# design.net
KiCad netlist of a schematic drawn in EasyEDA Pro
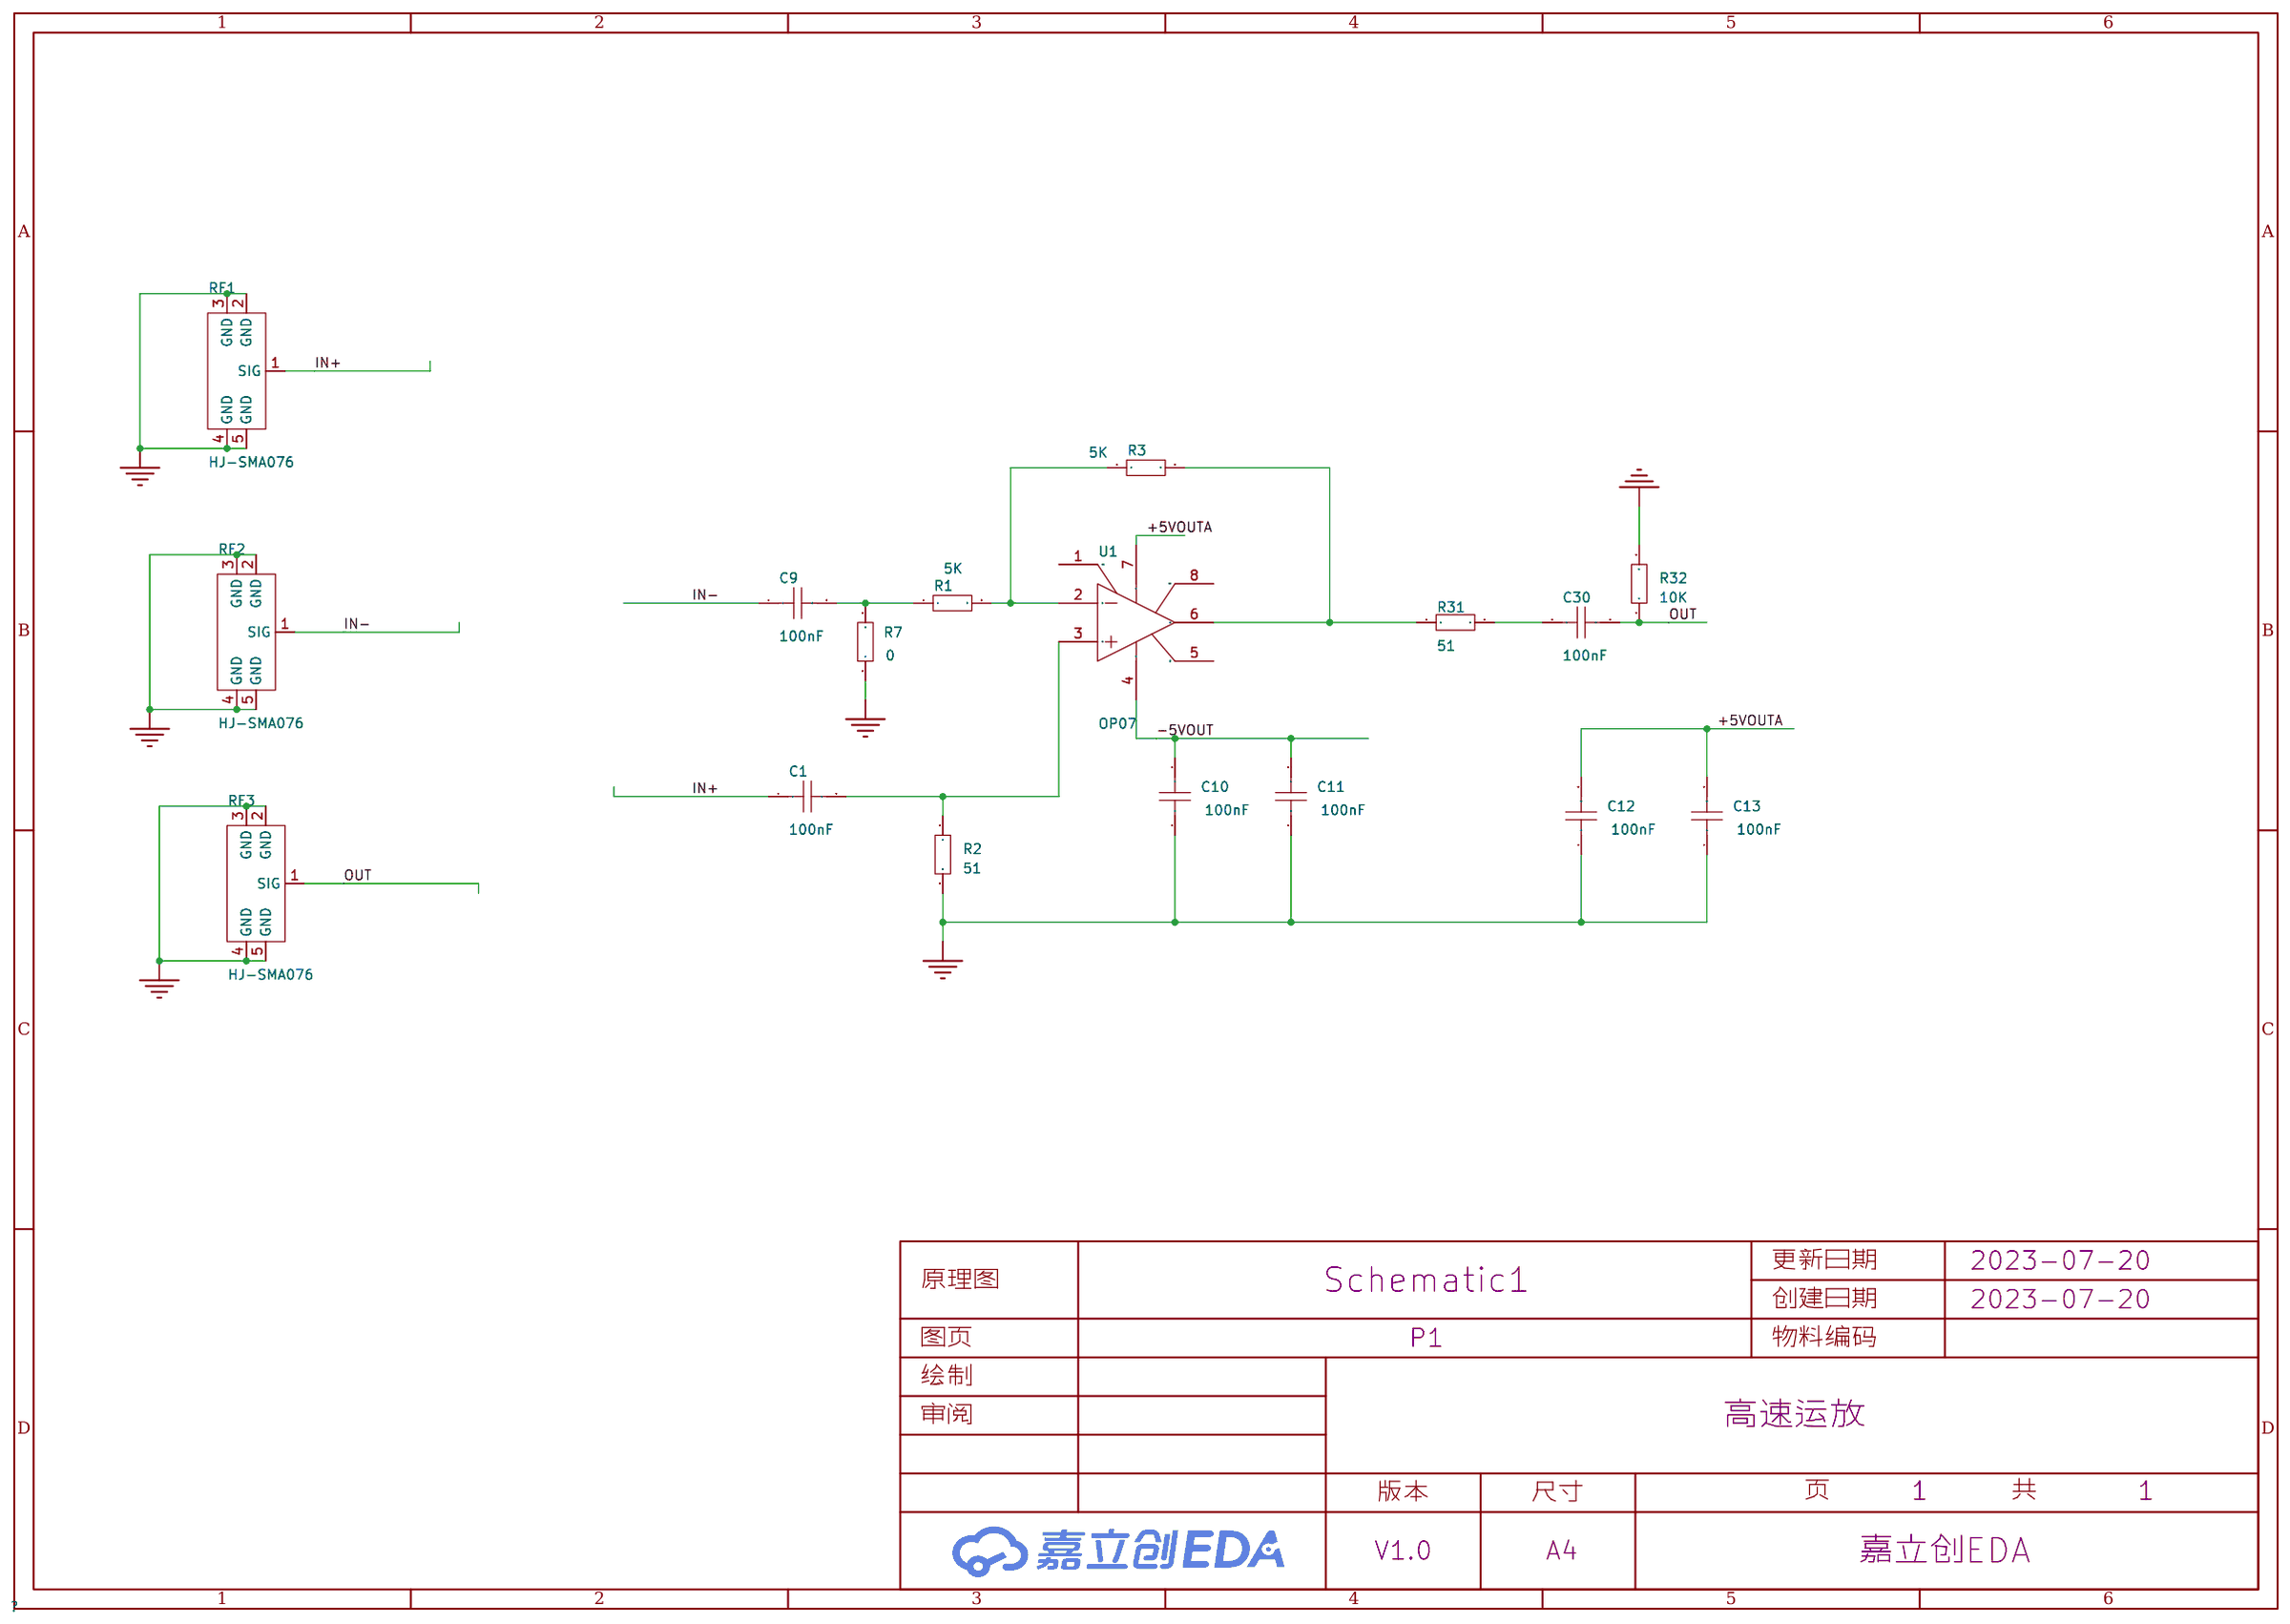
[diagram p0: P1]
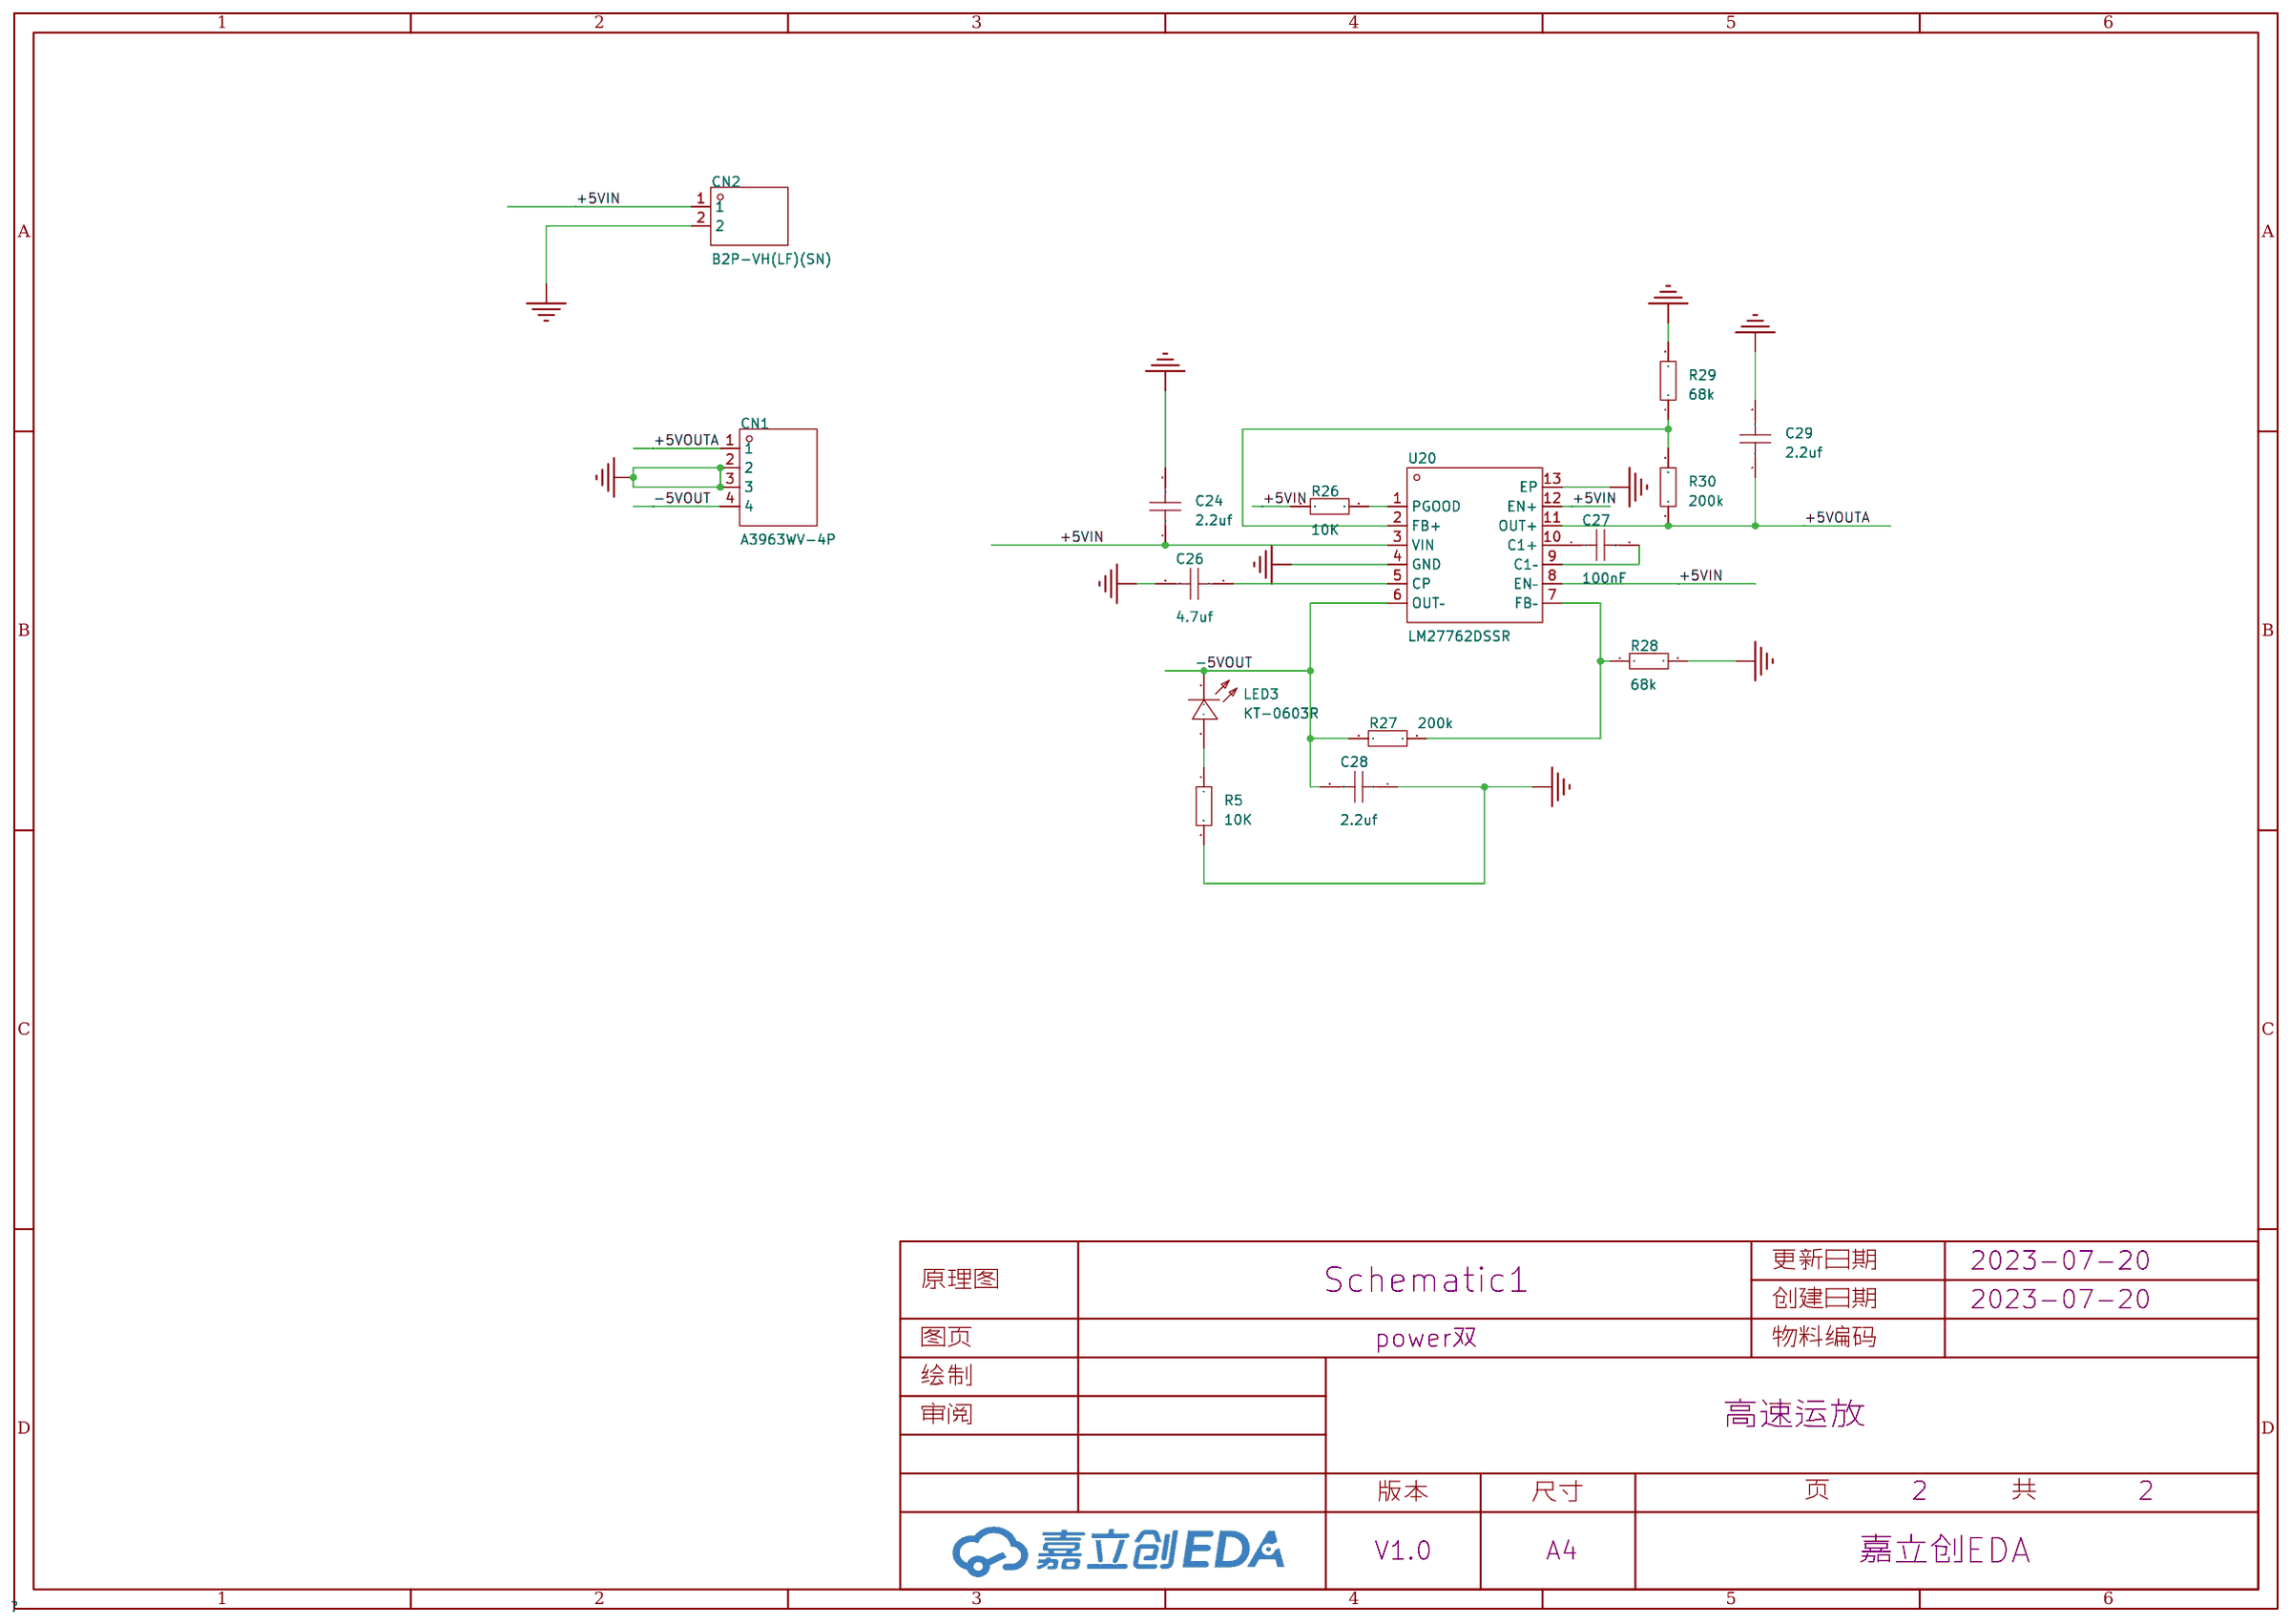
[diagram p1: power双]
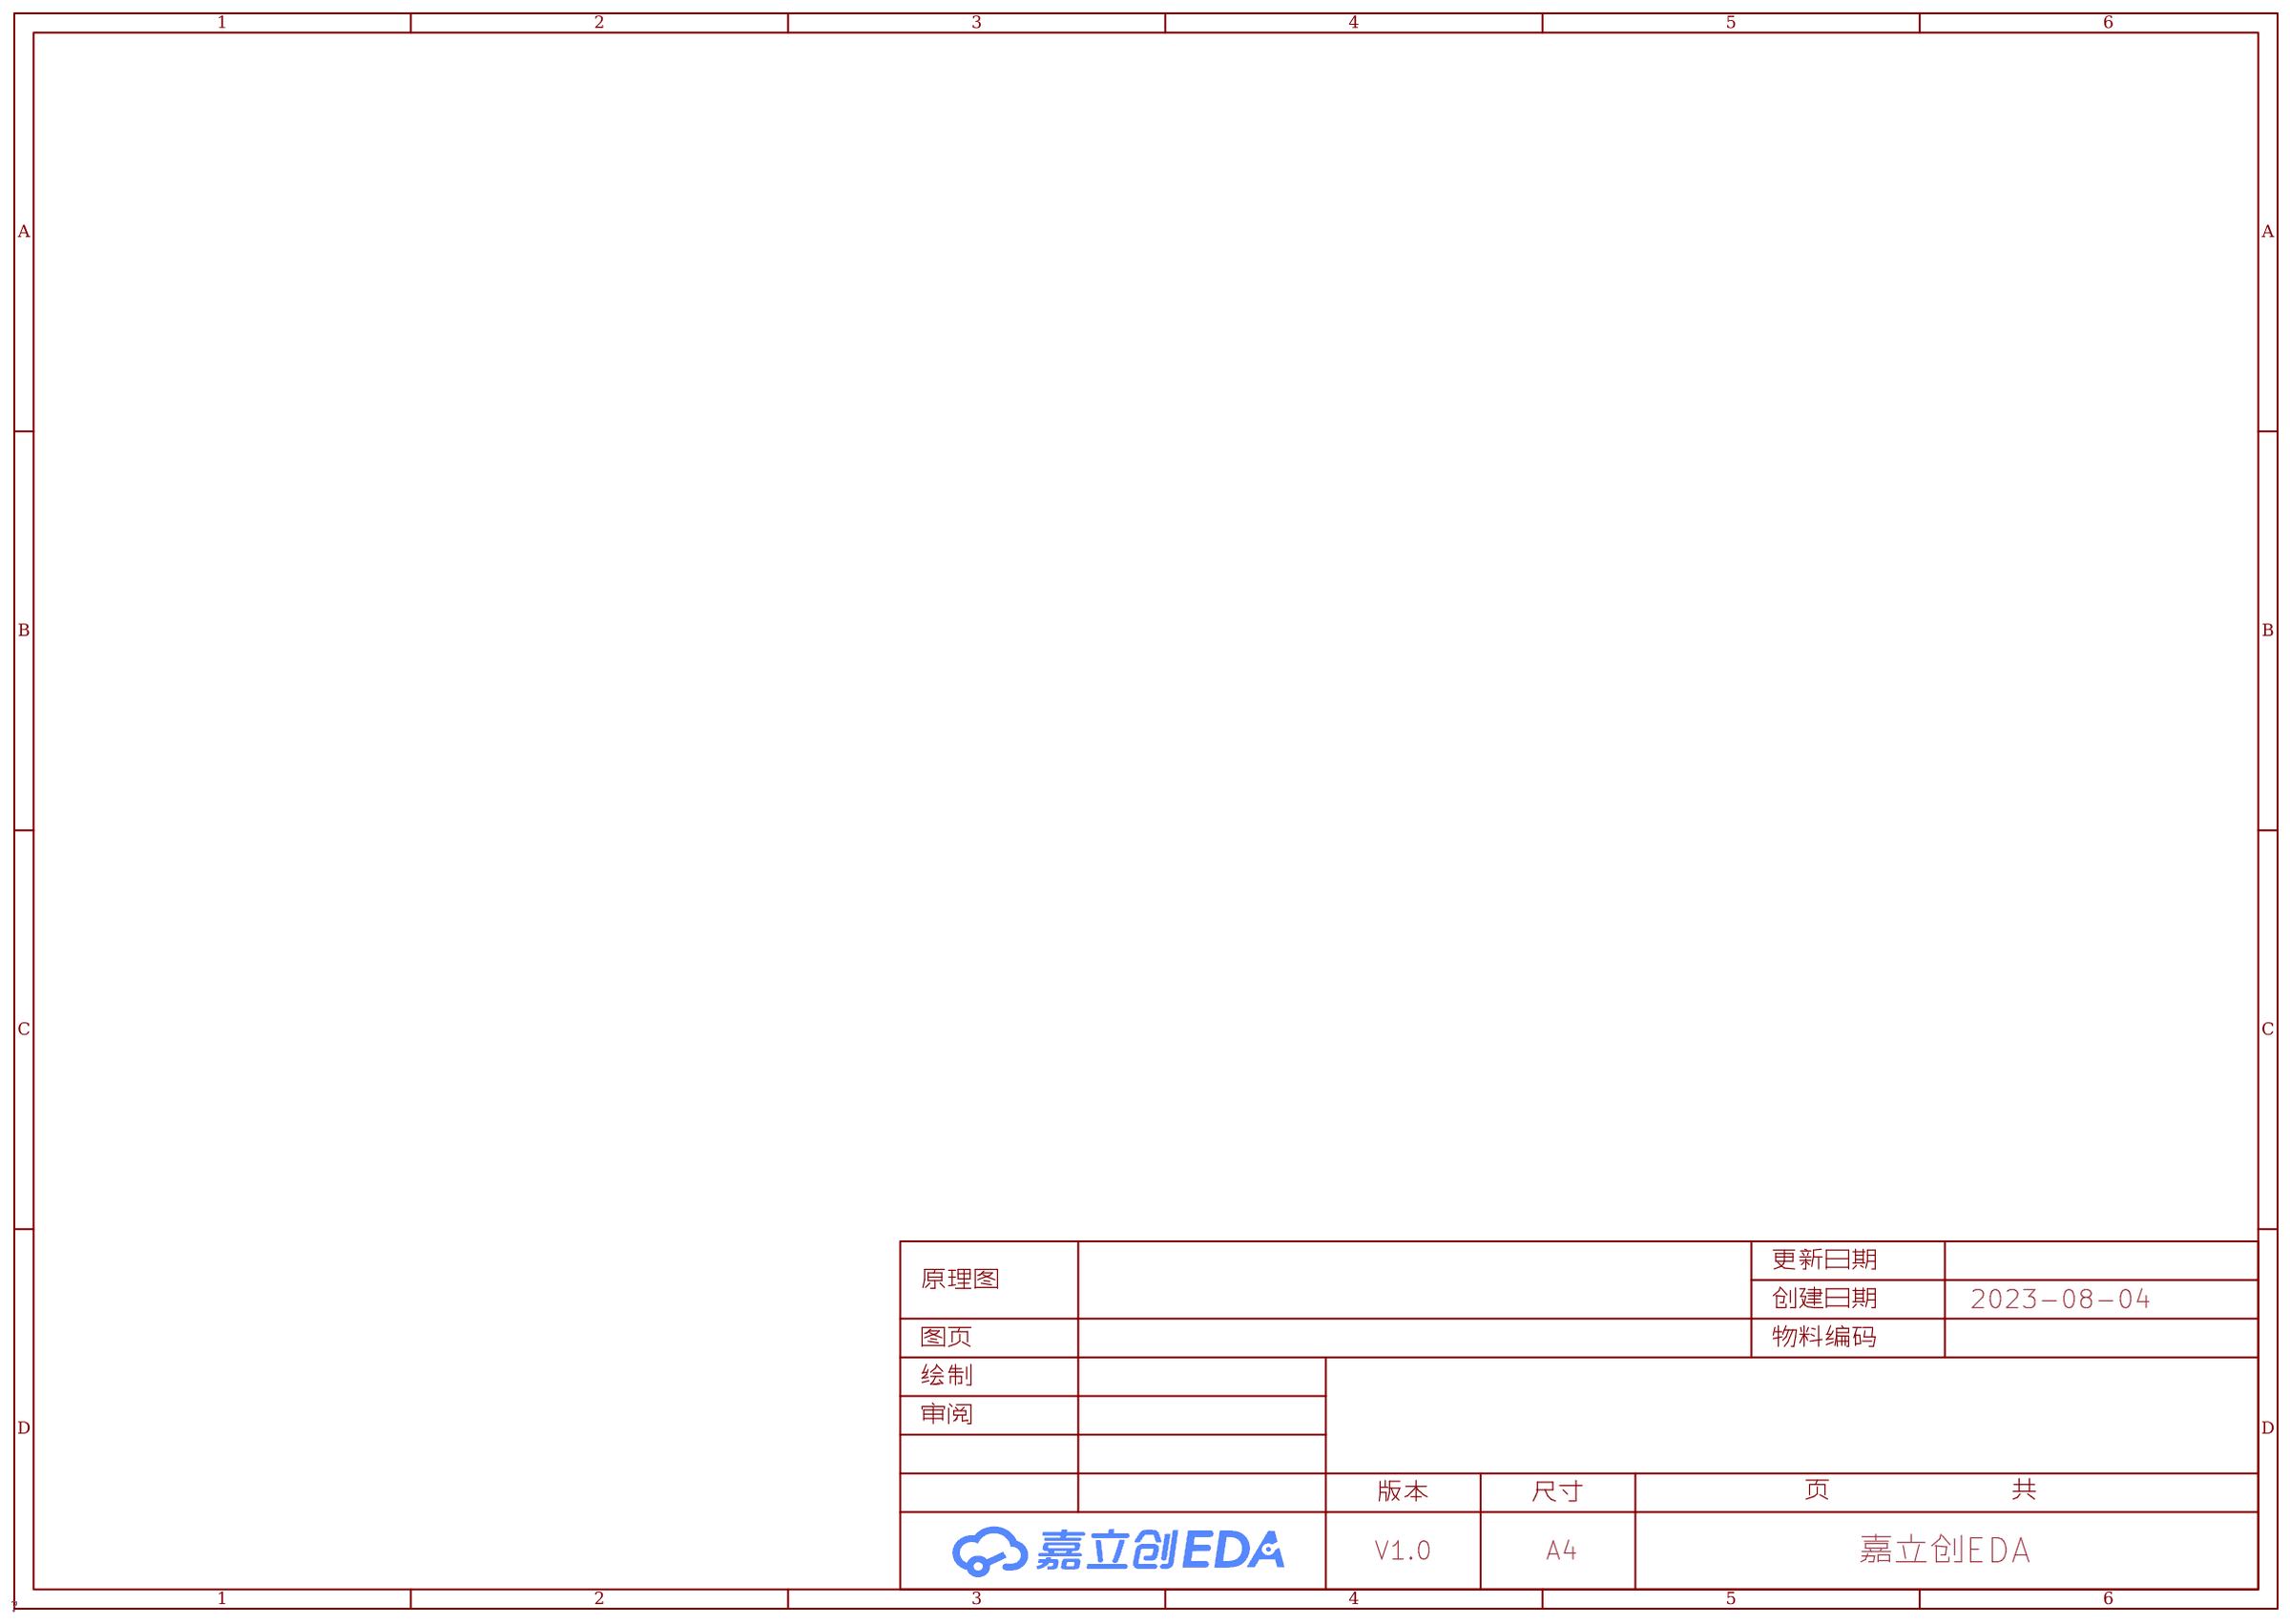
[diagram p2: P3]

(export (version "E")
  (design (tool "Eeschema 10.0.6"))
  (components
    (comp (ref "C1")
      (value "100nF")
      (footprint "easyedapro:C0603")
      (libsource (lib "easyedapro") (part "CapAcitance"))
    )
    (comp (ref "C9")
      (value "100nF")
      (footprint "easyedapro:C0603")
      (libsource (lib "easyedapro") (part "CapAcitance"))
    )
    (comp (ref "C10")
      (value "100nF")
      (footprint "easyedapro:C0603")
      (libsource (lib "easyedapro") (part "CapAcitance"))
    )
    (comp (ref "C11")
      (value "100nF")
      (footprint "easyedapro:C0603")
      (libsource (lib "easyedapro") (part "CapAcitance"))
    )
    (comp (ref "C12")
      (value "100nF")
      (footprint "easyedapro:C0603")
      (libsource (lib "easyedapro") (part "CapAcitance"))
    )
    (comp (ref "C13")
      (value "100nF")
      (footprint "easyedapro:C0603")
      (libsource (lib "easyedapro") (part "CapAcitance"))
    )
    (comp (ref "C30")
      (value "100nF")
      (footprint "easyedapro:C0603")
      (libsource (lib "easyedapro") (part "CapAcitance"))
    )
    (comp (ref "R1") (value "5K") (footprint "easyedapro:R0603") (libsource (lib "easyedapro") (part "电阻")))
    (comp (ref "R2") (value "51") (footprint "easyedapro:R0603") (libsource (lib "easyedapro") (part "电阻")))
    (comp (ref "R3") (value "5K") (footprint "easyedapro:R0603") (libsource (lib "easyedapro") (part "电阻")))
    (comp (ref "R7") (value "0") (footprint "easyedapro:R0603") (libsource (lib "easyedapro") (part "电阻")))
    (comp (ref "R31") (value "51") (footprint "easyedapro:R0603") (libsource (lib "easyedapro") (part "电阻")))
    (comp (ref "R32") (value "10K") (footprint "easyedapro:R0603") (libsource (lib "easyedapro") (part "电阻")))
    (comp (ref "RF1")
      (value "HJ-SMA076")
      (footprint "easyedapro:SMA-SMD_HJ-SMA076")
      (description "连接器类型:板端;射频系列:SMA;接口类型:内孔;端口数量:1;阻抗:-;频率-最大值:-;样式:偏脚;接口直径:-;接口长度/高度:-;工作温度范围:-;")
      (fields (field (name "Manufacturer") "皇捷"))
      (libsource (lib "easyedapro") (part "HJ-SMA076"))
    )
    (comp (ref "RF2")
      (value "HJ-SMA076")
      (footprint "easyedapro:SMA-SMD_HJ-SMA076")
      (description "连接器类型:板端;射频系列:SMA;接口类型:内孔;端口数量:1;阻抗:-;频率-最大值:-;样式:偏脚;接口直径:-;接口长度/高度:-;工作温度范围:-;")
      (fields (field (name "Manufacturer") "皇捷"))
      (libsource (lib "easyedapro") (part "HJ-SMA076"))
    )
    (comp (ref "RF3")
      (value "HJ-SMA076")
      (footprint "easyedapro:SMA-SMD_HJ-SMA076")
      (description "连接器类型:板端;射频系列:SMA;接口类型:内孔;端口数量:1;阻抗:-;频率-最大值:-;样式:偏脚;接口直径:-;接口长度/高度:-;工作温度范围:-;")
      (fields (field (name "Manufacturer") "皇捷"))
      (libsource (lib "easyedapro") (part "HJ-SMA076"))
    )
    (comp (ref "U1")
      (value "OP07")
      (footprint "easyedapro:SOP-8_L4.9-W3.9-P1.27-LS6.0-BL")
      (description "放大器组数:-;")
      (fields (field (name "Manufacturer") "杭州瑞盟"))
      (libsource (lib "easyedapro") (part "OP07"))
    )
    (comp (ref "C24")
      (value "2.2uf")
      (footprint "easyedapro:C0603")
      (libsource (lib "easyedapro") (part "CapAcitance"))
    )
    (comp (ref "C26")
      (value "4.7uf")
      (footprint "easyedapro:C0603")
      (libsource (lib "easyedapro") (part "CapAcitance"))
    )
    (comp (ref "C27")
      (value "100nF")
      (footprint "easyedapro:C0603")
      (libsource (lib "easyedapro") (part "CapAcitance"))
    )
    (comp (ref "C28")
      (value "2.2uf")
      (footprint "easyedapro:C0603")
      (libsource (lib "easyedapro") (part "CapAcitance"))
    )
    (comp (ref "C29")
      (value "2.2uf")
      (footprint "easyedapro:C0603")
      (libsource (lib "easyedapro") (part "CapAcitance"))
    )
    (comp (ref "CN1")
      (value "A3963WV-4P")
      (footprint "easyedapro:CONN-TH_A3963WV-4P")
      (description "参考系列:VH;间距:3.96mm;插针结构:1x4P;排数:1;每排PIN数:4;行距:-;安装方式:-;触头材质:黄铜;")
      (fields (field (name "Manufacturer") "CJT(长江连接器)"))
      (libsource (lib "easyedapro") (part "A3963WV-4P"))
    )
    (comp (ref "CN2")
      (value "B2P-VH(LF)(SN)")
      (footprint "easyedapro:CONN-TH_B2P-VH-LF-SN")
      (description "参考系列:VH;间距:3.96mm;插针结构:1x2P;排数:1;每排PIN数:2;行距:-;安装方式:-;触头材质:黄铜;")
      (fields (field (name "Manufacturer") "JST"))
      (libsource (lib "easyedapro") (part "B2P-VH (LF)(SN)"))
    )
    (comp (ref "LED3")
      (value "KT-0603R")
      (footprint "easyedapro:LED0603-RD")
      (description "发光颜色:红灯;二极管配置:-;透镜颜色:-;主波长:-;色温:-;功率:-;发光角度:-;安装方式:-;工作温度:-40℃~+85℃;")
      (fields (field (name "Manufacturer") "KENTO"))
      (libsource (lib "easyedapro") (part "KT-0603R"))
    )
    (comp (ref "R5") (value "10K") (footprint "easyedapro:R0603") (libsource (lib "easyedapro") (part "电阻")))
    (comp (ref "R26") (value "10K") (footprint "easyedapro:R0603") (libsource (lib "easyedapro") (part "电阻")))
    (comp (ref "R27")
      (value "200k")
      (footprint "easyedapro:R0603")
      (libsource (lib "easyedapro") (part "电阻"))
    )
    (comp (ref "R28") (value "68k") (footprint "easyedapro:R0603") (libsource (lib "easyedapro") (part "电阻")))
    (comp (ref "R29") (value "68k") (footprint "easyedapro:R0603") (libsource (lib "easyedapro") (part "电阻")))
    (comp (ref "R30")
      (value "200k")
      (footprint "easyedapro:R0603")
      (libsource (lib "easyedapro") (part "电阻"))
    )
    (comp (ref "U20")
      (value "LM27762DSSR")
      (footprint "easyedapro:WSON-12_L3.0-W2.0-P0.50-BL-EP")
      (description "功能类型:电荷泵;同步整流:否;输出通道数:2;拓扑结构:-;输入电压:2.7V~5.5V;输出电压:-5V~-1.5V；1.5V~5V;输出电流(最大值):250mA;开关频率:2.3MHz;")
      (fields (field (name "Manufacturer") "TI(德州仪器)"))
      (libsource (lib "easyedapro") (part "LM27762DSSR"))
    )
  )
  (nets
    (net (code "1") (name "+5VIN") (class "Default")
      (node (ref "C24") (pin "1") (pinfunction "1_1") (pintype "input"))
      (node (ref "CN2") (pin "1") (pinfunction "1_1") (pintype "input"))
      (node (ref "R26") (pin "1") (pinfunction "1_1") (pintype "input"))
      (node (ref "U20") (pin "12") (pinfunction "EN+_12") (pintype "input"))
      (node (ref "U20") (pin "3") (pinfunction "VIN_3") (pintype "input"))
      (node (ref "U20") (pin "8") (pinfunction "EN–_8") (pintype "input"))
    )
    (net (code "2") (name "+5VOUTA") (class "Default")
      (node (ref "C12") (pin "2") (pinfunction "2_2") (pintype "input"))
      (node (ref "C13") (pin "2") (pinfunction "2_2") (pintype "input"))
      (node (ref "C29") (pin "1") (pinfunction "1_1") (pintype "input"))
      (node (ref "CN1") (pin "1") (pinfunction "1_1") (pintype "input"))
      (node (ref "R30") (pin "1") (pinfunction "1_1") (pintype "input"))
      (node (ref "U1") (pin "7") (pinfunction "V+_7") (pintype "input"))
      (node (ref "U20") (pin "11") (pinfunction "OUT+_11") (pintype "input"))
    )
    (net (code "3") (name "-5VOUT") (class "Default")
      (node (ref "C10") (pin "2") (pinfunction "2_2") (pintype "input"))
      (node (ref "C11") (pin "2") (pinfunction "2_2") (pintype "input"))
      (node (ref "C28") (pin "2") (pinfunction "2_2") (pintype "input"))
      (node (ref "CN1") (pin "4") (pinfunction "4_4") (pintype "input"))
      (node (ref "LED3") (pin "1") (pinfunction "K_1") (pintype "input"))
      (node (ref "R27") (pin "1") (pinfunction "1_1") (pintype "input"))
      (node (ref "U1") (pin "4") (pinfunction "V-_4") (pintype "input"))
      (node (ref "U20") (pin "6") (pinfunction "OUT–_6") (pintype "input"))
    )
    (net (code "4") (name "GND") (class "Default")
      (node (ref "C10") (pin "1") (pinfunction "1_1") (pintype "input"))
      (node (ref "C11") (pin "1") (pinfunction "1_1") (pintype "input"))
      (node (ref "C12") (pin "1") (pinfunction "1_1") (pintype "input"))
      (node (ref "C13") (pin "1") (pinfunction "1_1") (pintype "input"))
      (node (ref "C24") (pin "2") (pinfunction "2_2") (pintype "input"))
      (node (ref "C26") (pin "2") (pinfunction "2_2") (pintype "input"))
      (node (ref "C28") (pin "1") (pinfunction "1_1") (pintype "input"))
      (node (ref "C29") (pin "2") (pinfunction "2_2") (pintype "input"))
      (node (ref "CN1") (pin "2") (pinfunction "2_2") (pintype "input"))
      (node (ref "CN1") (pin "3") (pinfunction "3_3") (pintype "input"))
      (node (ref "CN2") (pin "2") (pinfunction "2_2") (pintype "input"))
      (node (ref "R2") (pin "2") (pinfunction "2_2") (pintype "input"))
      (node (ref "R28") (pin "2") (pinfunction "2_2") (pintype "input"))
      (node (ref "R29") (pin "2") (pinfunction "2_2") (pintype "input"))
      (node (ref "R32") (pin "2") (pinfunction "2_2") (pintype "input"))
      (node (ref "R5") (pin "2") (pinfunction "2_2") (pintype "input"))
      (node (ref "R7") (pin "1") (pinfunction "1_1") (pintype "input"))
      (node (ref "RF1") (pin "2") (pinfunction "GND_2") (pintype "input"))
      (node (ref "RF1") (pin "3") (pinfunction "GND_3") (pintype "input"))
      (node (ref "RF1") (pin "4") (pinfunction "GND_4") (pintype "input"))
      (node (ref "RF1") (pin "5") (pinfunction "GND_5") (pintype "input"))
      (node (ref "RF2") (pin "2") (pinfunction "GND_2") (pintype "input"))
      (node (ref "RF2") (pin "3") (pinfunction "GND_3") (pintype "input"))
      (node (ref "RF2") (pin "4") (pinfunction "GND_4") (pintype "input"))
      (node (ref "RF2") (pin "5") (pinfunction "GND_5") (pintype "input"))
      (node (ref "RF3") (pin "2") (pinfunction "GND_2") (pintype "input"))
      (node (ref "RF3") (pin "3") (pinfunction "GND_3") (pintype "input"))
      (node (ref "RF3") (pin "4") (pinfunction "GND_4") (pintype "input"))
      (node (ref "RF3") (pin "5") (pinfunction "GND_5") (pintype "input"))
      (node (ref "U20") (pin "13") (pinfunction "EP_13") (pintype "input"))
      (node (ref "U20") (pin "4") (pinfunction "GND_4") (pintype "input"))
    )
    (net (code "5") (name "IN+") (class "Default")
      (node (ref "C1") (pin "1") (pinfunction "1_1") (pintype "input"))
      (node (ref "RF1") (pin "1") (pinfunction "SIG_1") (pintype "input"))
    )
    (net (code "6") (name "IN-") (class "Default")
      (node (ref "C9") (pin "1") (pinfunction "1_1") (pintype "input"))
      (node (ref "RF2") (pin "1") (pinfunction "SIG_1") (pintype "input"))
    )
    (net (code "7") (name "Net-(C9-Pad2)") (class "Default")
      (node (ref "C9") (pin "2") (pinfunction "2_2") (pintype "input"))
      (node (ref "R1") (pin "1") (pinfunction "1_1") (pintype "input"))
      (node (ref "R7") (pin "2") (pinfunction "2_2") (pintype "input"))
    )
    (net (code "8") (name "Net-(C30-Pad1)") (class "Default")
      (node (ref "C30") (pin "1") (pinfunction "1_1") (pintype "input"))
      (node (ref "R31") (pin "1") (pinfunction "1_1") (pintype "input"))
    )
    (net (code "9") (name "Net-(LED3-A)") (class "Default")
      (node (ref "LED3") (pin "2") (pinfunction "A_2") (pintype "input"))
      (node (ref "R5") (pin "1") (pinfunction "1_1") (pintype "input"))
    )
    (net (code "10") (name "Net-(U1-IN+)") (class "Default")
      (node (ref "C1") (pin "2") (pinfunction "2_2") (pintype "input"))
      (node (ref "R2") (pin "1") (pinfunction "1_1") (pintype "input"))
      (node (ref "U1") (pin "3") (pinfunction "IN+_3") (pintype "input"))
    )
    (net (code "11") (name "Net-(U1-IN-)") (class "Default")
      (node (ref "R1") (pin "2") (pinfunction "2_2") (pintype "input"))
      (node (ref "R3") (pin "1") (pinfunction "1_1") (pintype "input"))
      (node (ref "U1") (pin "2") (pinfunction "IN-_2") (pintype "input"))
    )
    (net (code "12") (name "Net-(U1-OUT)") (class "Default")
      (node (ref "R3") (pin "2") (pinfunction "2_2") (pintype "input"))
      (node (ref "R31") (pin "2") (pinfunction "2_2") (pintype "input"))
      (node (ref "U1") (pin "6") (pinfunction "OUT_6") (pintype "output"))
    )
    (net (code "13") (name "Net-(U20-C1+)") (class "Default")
      (node (ref "C27") (pin "1") (pinfunction "1_1") (pintype "input"))
      (node (ref "U20") (pin "10") (pinfunction "C1+_10") (pintype "input"))
    )
    (net (code "14") (name "Net-(U20-C1–)") (class "Default")
      (node (ref "C27") (pin "2") (pinfunction "2_2") (pintype "input"))
      (node (ref "U20") (pin "9") (pinfunction "C1–_9") (pintype "input"))
    )
    (net (code "15") (name "Net-(U20-CP)") (class "Default")
      (node (ref "C26") (pin "1") (pinfunction "1_1") (pintype "input"))
      (node (ref "U20") (pin "5") (pinfunction "CP_5") (pintype "input"))
    )
    (net (code "16") (name "Net-(U20-FB+)") (class "Default")
      (node (ref "R29") (pin "1") (pinfunction "1_1") (pintype "input"))
      (node (ref "R30") (pin "2") (pinfunction "2_2") (pintype "input"))
      (node (ref "U20") (pin "2") (pinfunction "FB+_2") (pintype "input"))
    )
    (net (code "17") (name "Net-(U20-FB–)") (class "Default")
      (node (ref "R27") (pin "2") (pinfunction "2_2") (pintype "input"))
      (node (ref "R28") (pin "1") (pinfunction "1_1") (pintype "input"))
      (node (ref "U20") (pin "7") (pinfunction "FB–_7") (pintype "input"))
    )
    (net (code "18") (name "Net-(U20-PGOOD)") (class "Default")
      (node (ref "R26") (pin "2") (pinfunction "2_2") (pintype "input"))
      (node (ref "U20") (pin "1") (pinfunction "PGOOD_1") (pintype "input"))
    )
    (net (code "19") (name "OUT") (class "Default")
      (node (ref "C30") (pin "2") (pinfunction "2_2") (pintype "input"))
      (node (ref "R32") (pin "1") (pinfunction "1_1") (pintype "input"))
      (node (ref "RF3") (pin "1") (pinfunction "SIG_1") (pintype "input"))
    )
    (net (code "20") (name "unconnected-(U1-NC-Pad5)") (class "Default")
      (node (ref "U1") (pin "5") (pinfunction "NC_5") (pintype "input"))
    )
    (net (code "21") (name "unconnected-(U1-VOS_TRIM-Pad1)") (class "Default")
      (node (ref "U1") (pin "1") (pinfunction "VOS_TRIM_1") (pintype "input"))
    )
    (net (code "22") (name "unconnected-(U1-VOS_TRIM-Pad8)") (class "Default")
      (node (ref "U1") (pin "8") (pinfunction "VOS_TRIM_8") (pintype "input"))
    )
  )
)
